# Sch_pengusir_hama_pcb.net
KiCad netlist of a schematic drawn in EAGLE
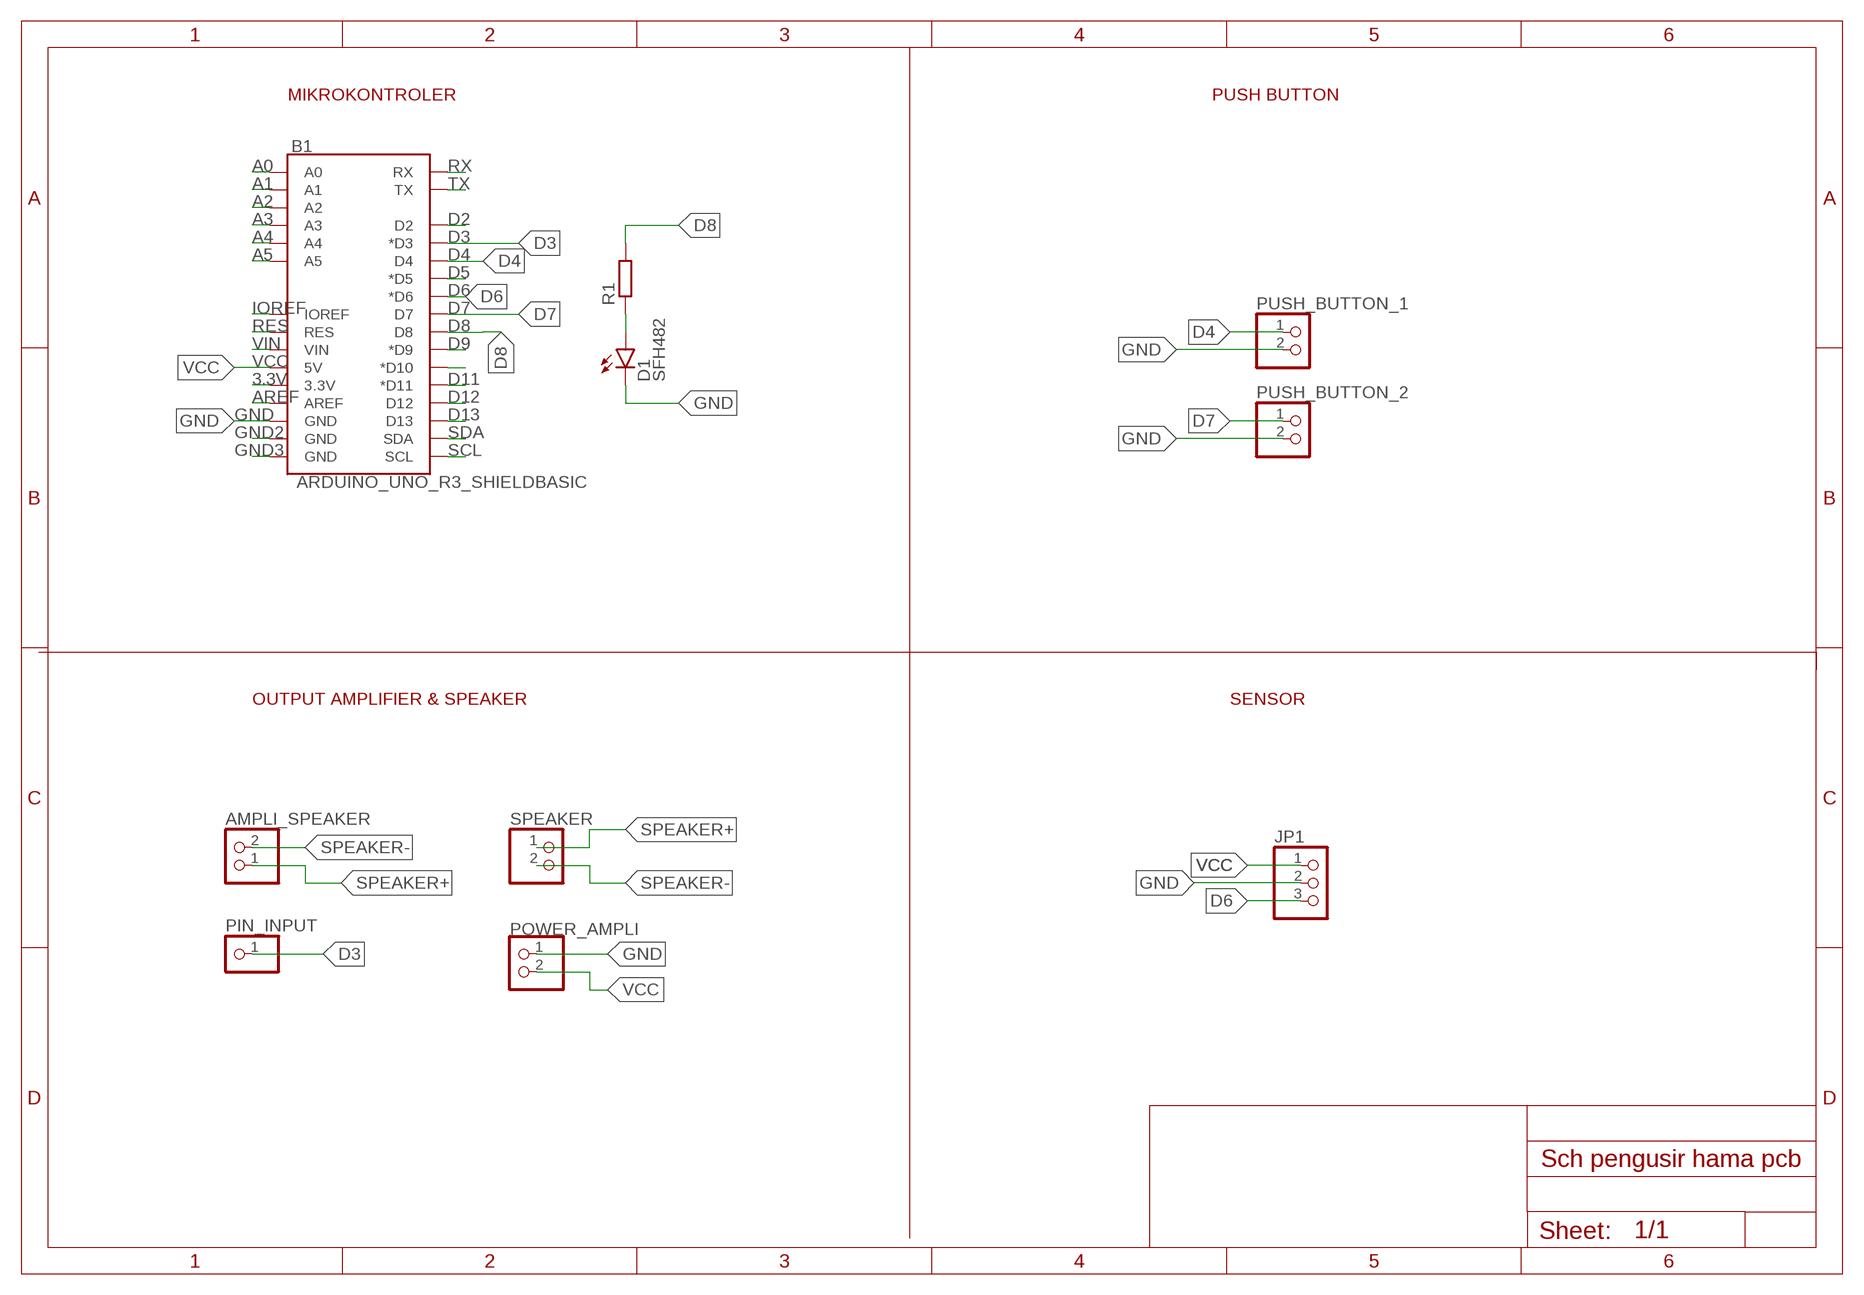
[diagram p0: schematic, sheet 1]

(export (version "E")
  (design (tool "Eeschema 10.0.6"))
  (components
    (comp (ref "AMPLI_SPEAKER")
      (value "PINHD-1X2")
      (footprint "eagle-import:1X02")
      (libsource (lib "eagle-import") (part "PINHD-1X2"))
    )
    (comp (ref "B1")
      (value "ARDUINO_UNO_R3_SHIELDBASIC")
      (footprint "eagle-import:UNO_R3_SHIELD")
      (libsource (lib "eagle-import") (part "ARDUINO_UNO_R3_SHIELDBASIC"))
    )
    (comp (ref "D1")
      (value "SFH482")
      (footprint "eagle-import:SFH482")
      (libsource (lib "eagle-import") (part "SFH482"))
    )
    (comp (ref "JP1")
      (value "PINHD-1X3")
      (footprint "eagle-import:1X03")
      (libsource (lib "eagle-import") (part "PINHD-1X3"))
    )
    (comp (ref "PIN_INPUT")
      (value "PINHD-1X1")
      (footprint "eagle-import:1X01")
      (libsource (lib "eagle-import") (part "PINHD-1X1"))
    )
    (comp (ref "POWER_AMPLI")
      (value "PINHD-1X2")
      (footprint "eagle-import:1X02")
      (libsource (lib "eagle-import") (part "PINHD-1X2"))
    )
    (comp (ref "PUSH_BUTTON_1")
      (value "PINHD-1X2")
      (footprint "eagle-import:1X02")
      (libsource (lib "eagle-import") (part "PINHD-1X2"))
    )
    (comp (ref "PUSH_BUTTON_2")
      (value "PINHD-1X2")
      (footprint "eagle-import:1X02")
      (libsource (lib "eagle-import") (part "PINHD-1X2"))
    )
    (comp (ref "R1")
      (value "R-EU_0207/7")
      (footprint "eagle-import:0207_7")
      (libsource (lib "eagle-import") (part "R-EU_0207/7"))
    )
    (comp (ref "SPEAKER")
      (value "PINHD-1X2")
      (footprint "eagle-import:1X02")
      (libsource (lib "eagle-import") (part "PINHD-1X2"))
    )
  )
  (nets
    (net (code "1") (name "/3.3V") (class "Default")
      (node (ref "B1") (pin "3.3V") (pinfunction "3.3V_3.3V") (pintype "bidirectional"))
    )
    (net (code "2") (name "/A0") (class "Default")
      (node (ref "B1") (pin "A0") (pinfunction "A0_A0") (pintype "bidirectional"))
    )
    (net (code "3") (name "/A1") (class "Default")
      (node (ref "B1") (pin "A1") (pinfunction "A1_A1") (pintype "bidirectional"))
    )
    (net (code "4") (name "/A2") (class "Default")
      (node (ref "B1") (pin "A2") (pinfunction "A2_A2") (pintype "bidirectional"))
    )
    (net (code "5") (name "/A3") (class "Default")
      (node (ref "B1") (pin "A3") (pinfunction "A3_A3") (pintype "bidirectional"))
    )
    (net (code "6") (name "/A4") (class "Default")
      (node (ref "B1") (pin "A4") (pinfunction "A4_A4") (pintype "bidirectional"))
    )
    (net (code "7") (name "/A5") (class "Default")
      (node (ref "B1") (pin "A5") (pinfunction "A5_A5") (pintype "bidirectional"))
    )
    (net (code "8") (name "/AREF") (class "Default")
      (node (ref "B1") (pin "AREF") (pinfunction "AREF_AREF") (pintype "bidirectional"))
    )
    (net (code "9") (name "/D2") (class "Default")
      (node (ref "B1") (pin "D2") (pinfunction "D2_D2") (pintype "bidirectional"))
    )
    (net (code "10") (name "/D5") (class "Default")
      (node (ref "B1") (pin "D5") (pinfunction "*D5_D5") (pintype "bidirectional"))
    )
    (net (code "11") (name "/D9") (class "Default")
      (node (ref "B1") (pin "D9") (pinfunction "*D9_D9") (pintype "bidirectional"))
    )
    (net (code "12") (name "/D11") (class "Default")
      (node (ref "B1") (pin "D11") (pinfunction "*D11_D11") (pintype "bidirectional"))
    )
    (net (code "13") (name "/D12") (class "Default")
      (node (ref "B1") (pin "D12") (pinfunction "D12_D12") (pintype "bidirectional"))
    )
    (net (code "14") (name "/D13") (class "Default")
      (node (ref "B1") (pin "D13") (pinfunction "D13_D13") (pintype "bidirectional"))
    )
    (net (code "15") (name "/GND2") (class "Default")
      (node (ref "B1") (pin "GND@1") (pinfunction "GND_GND@1") (pintype "bidirectional"))
    )
    (net (code "16") (name "/GND3") (class "Default")
      (node (ref "B1") (pin "GND@0") (pinfunction "GND_GND@0") (pintype "bidirectional"))
    )
    (net (code "17") (name "/IOREF") (class "Default")
      (node (ref "B1") (pin "IOREF") (pinfunction "IOREF_IOREF") (pintype "bidirectional"))
    )
    (net (code "18") (name "/RES") (class "Default")
      (node (ref "B1") (pin "RES") (pinfunction "RES_RES") (pintype "bidirectional"))
    )
    (net (code "19") (name "/RX") (class "Default")
      (node (ref "B1") (pin "RX") (pinfunction "RX_RX") (pintype "bidirectional"))
    )
    (net (code "20") (name "/SCL") (class "Default")
      (node (ref "B1") (pin "SCL") (pinfunction "SCL_SCL") (pintype "bidirectional"))
    )
    (net (code "21") (name "/SDA") (class "Default")
      (node (ref "B1") (pin "SDA") (pinfunction "SDA_SDA") (pintype "bidirectional"))
    )
    (net (code "22") (name "/TX") (class "Default")
      (node (ref "B1") (pin "TX") (pinfunction "TX_TX") (pintype "bidirectional"))
    )
    (net (code "23") (name "/VIN") (class "Default")
      (node (ref "B1") (pin "VIN") (pinfunction "VIN_VIN") (pintype "bidirectional"))
    )
    (net (code "24") (name "D3") (class "Default")
      (node (ref "B1") (pin "D3") (pinfunction "*D3_D3") (pintype "bidirectional"))
      (node (ref "PIN_INPUT") (pin "1") (pinfunction "1_1") (pintype "passive"))
    )
    (net (code "25") (name "D4") (class "Default")
      (node (ref "B1") (pin "D4") (pinfunction "D4_D4") (pintype "bidirectional"))
      (node (ref "PUSH_BUTTON_1") (pin "1") (pinfunction "1_1") (pintype "passive"))
    )
    (net (code "26") (name "D6") (class "Default")
      (node (ref "B1") (pin "D6") (pinfunction "*D6_D6") (pintype "bidirectional"))
      (node (ref "JP1") (pin "3") (pinfunction "3_3") (pintype "passive"))
    )
    (net (code "27") (name "D7") (class "Default")
      (node (ref "B1") (pin "D7") (pinfunction "D7_D7") (pintype "bidirectional"))
      (node (ref "PUSH_BUTTON_2") (pin "1") (pinfunction "1_1") (pintype "passive"))
    )
    (net (code "28") (name "D8") (class "Default")
      (node (ref "B1") (pin "D8") (pinfunction "D8_D8") (pintype "bidirectional"))
      (node (ref "R1") (pin "2") (pinfunction "2_2") (pintype "passive"))
    )
    (net (code "29") (name "GND") (class "Default")
      (node (ref "B1") (pin "GND@2") (pinfunction "GND_GND@2") (pintype "bidirectional"))
      (node (ref "D1") (pin "K") (pinfunction "C_K") (pintype "passive"))
      (node (ref "JP1") (pin "2") (pinfunction "2_2") (pintype "passive"))
      (node (ref "POWER_AMPLI") (pin "1") (pinfunction "1_1") (pintype "passive"))
      (node (ref "PUSH_BUTTON_1") (pin "2") (pinfunction "2_2") (pintype "passive"))
      (node (ref "PUSH_BUTTON_2") (pin "2") (pinfunction "2_2") (pintype "passive"))
    )
    (net (code "30") (name "Net-(D1-PadA)") (class "Default")
      (node (ref "D1") (pin "A") (pinfunction "A_A") (pintype "passive"))
      (node (ref "R1") (pin "1") (pinfunction "1_1") (pintype "passive"))
    )
    (net (code "31") (name "SPEAKER+") (class "Default")
      (node (ref "AMPLI_SPEAKER") (pin "1") (pinfunction "1_1") (pintype "passive"))
      (node (ref "SPEAKER") (pin "1") (pinfunction "1_1") (pintype "passive"))
    )
    (net (code "32") (name "SPEAKER-") (class "Default")
      (node (ref "AMPLI_SPEAKER") (pin "2") (pinfunction "2_2") (pintype "passive"))
      (node (ref "SPEAKER") (pin "2") (pinfunction "2_2") (pintype "passive"))
    )
    (net (code "33") (name "VCC") (class "Default")
      (node (ref "B1") (pin "5V") (pinfunction "5V_5V") (pintype "bidirectional"))
      (node (ref "JP1") (pin "1") (pinfunction "1_1") (pintype "passive"))
      (node (ref "POWER_AMPLI") (pin "2") (pinfunction "2_2") (pintype "passive"))
    )
    (net (code "34") (name "unconnected-(B1-*D10-PadD10)") (class "Default")
      (node (ref "B1") (pin "D10") (pinfunction "*D10_D10") (pintype "bidirectional"))
    )
  )
)
